# V2.net
KiCad netlist of a schematic drawn in Altium Designer
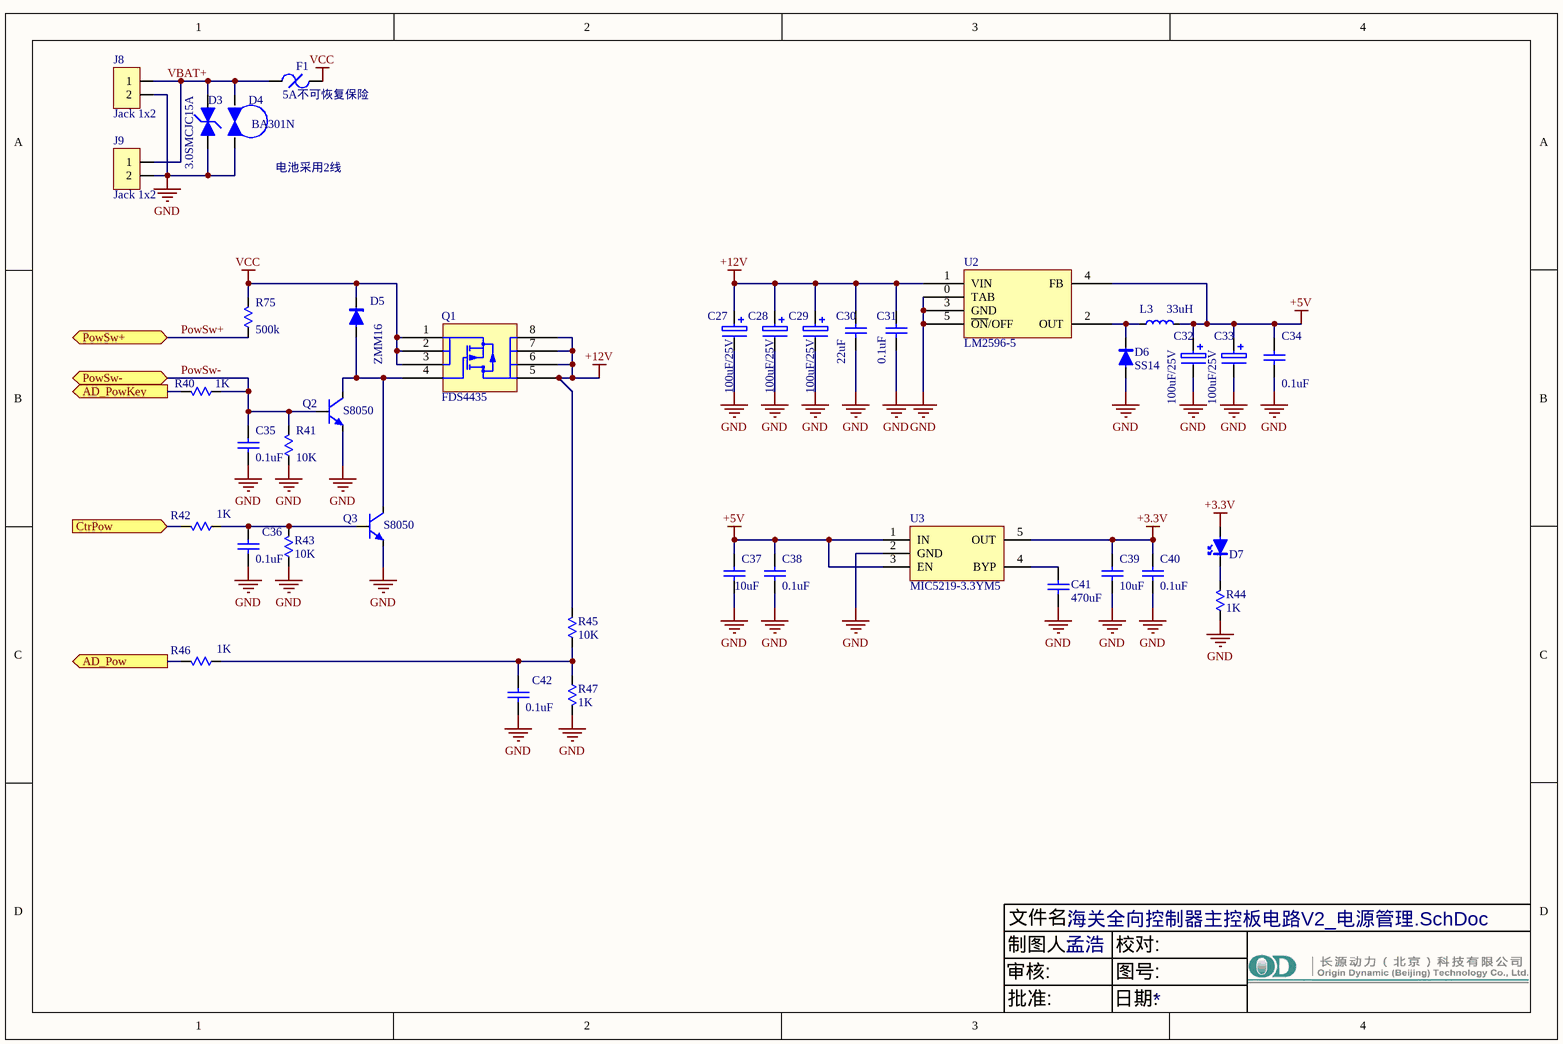
[diagram p0: 海关全向控制器主控板电路V2_电源管理.SchDoc]

(export (version "E")
  (design (tool "Eeschema 10.0.6"))
  (components
    (comp (ref "C27") (value "100uF/25V") (footprint "C7343") (libsource (lib "RLCYDF") (part "Cap Poll")))
    (comp (ref "C28") (value "100uF/25V") (footprint "C7343") (libsource (lib "RLCYDF") (part "Cap Poll")))
    (comp (ref "C29") (value "100uF/25V") (footprint "C7343") (libsource (lib "RLCYDF") (part "Cap Poll")))
    (comp (ref "C30")
      (value "22uF")
      (footprint "C1206")
      (description "CAP")
      (fields (field (name "PUBLISHER") "Altium Limited"))
      (libsource (lib "Passive Components Class") (part "CAP"))
    )
    (comp (ref "C31")
      (value "0.1uF")
      (footprint "C1206")
      (description "CAP")
      (fields (field (name "PUBLISHER") "Altium Limited"))
      (libsource (lib "Passive Components Class") (part "CAP"))
    )
    (comp (ref "C32")
      (value "100uF/25V")
      (footprint "C7343")
      (description "Electrolytic Capacitor")
      (libsource (lib "*") (part "ELECTRO"))
    )
    (comp (ref "C33")
      (value "100uF/25V")
      (footprint "C7343")
      (description "Electrolytic Capacitor")
      (libsource (lib "*") (part "ELECTRO"))
    )
    (comp (ref "C34")
      (value "0.1uF")
      (footprint "C0603")
      (description "CAP")
      (fields (field (name "PUBLISHER") "Altium Limited"))
      (libsource (lib "Passive Components Class") (part "CAP"))
    )
    (comp (ref "C35")
      (value "0.1uF")
      (footprint "C0603")
      (description "CAP")
      (fields (field (name "PUBLISHER") "Altium Limited"))
      (libsource (lib "Passive Components Class") (part "CAP"))
    )
    (comp (ref "C36")
      (value "0.1uF")
      (footprint "C0603")
      (description "CAP")
      (fields (field (name "PUBLISHER") "Altium Limited"))
      (libsource (lib "Passive Components Class") (part "CAP"))
    )
    (comp (ref "C37")
      (value "10uF")
      (footprint "C0603")
      (description "CAP")
      (fields (field (name "PUBLISHER") "Altium Limited"))
      (libsource (lib "Passive Components Class") (part "CAP"))
    )
    (comp (ref "C38")
      (value "0.1uF")
      (footprint "C0603")
      (description "CAP")
      (fields (field (name "PUBLISHER") "Altium Limited"))
      (libsource (lib "Passive Components Class") (part "CAP"))
    )
    (comp (ref "C39")
      (value "10uF")
      (footprint "C0603")
      (description "CAP")
      (fields (field (name "PUBLISHER") "Altium Limited"))
      (libsource (lib "Passive Components Class") (part "CAP"))
    )
    (comp (ref "C40")
      (value "0.1uF")
      (footprint "C0603")
      (description "CAP")
      (fields (field (name "PUBLISHER") "Altium Limited"))
      (libsource (lib "Passive Components Class") (part "CAP"))
    )
    (comp (ref "C41") (value "470uF") (footprint "C0603") (libsource (lib "SMD") (part "Cap Semi")))
    (comp (ref "C42")
      (value "0.1uF")
      (footprint "C0603")
      (description "CAP")
      (fields (field (name "PUBLISHER") "Altium Limited"))
      (libsource (lib "Passive Components Class") (part "CAP"))
    )
    (comp (ref "D3") (value "3.0SMCJC15A") (footprint "smc") (libsource (lib "RLCYDF") (part "Diode-TVS")))
    (comp (ref "D4") (value "BA301N") (footprint "BA301N") (libsource (lib "MhSchlib") (part "BA301N")))
    (comp (ref "D5")
      (value "ZMM16")
      (footprint "SOD-80-S")
      (description "Small Signal Zener Diodes")
      (libsource (lib "Passive Components Class") (part "DIODE-ZENER"))
    )
    (comp (ref "D6")
      (value "SS14")
      (footprint "SMA")
      (description "Silicon Epitaxial Planar Diodes")
      (libsource (lib "RLCYDF") (part "Diode-Switch"))
    )
    (comp (ref "D7")
      (value "LED")
      (footprint "LED0603")
      (libsource (lib "Passive Components Class") (part "LED"))
    )
    (comp (ref "F1") (value "5A不可恢复保险") (footprint "F1218") (libsource (lib "RLCYDF") (part "Fuse2")))
    (comp (ref "J8")
      (value "Jack 1x2")
      (footprint "ZH-2AWD")
      (description "插座")
      (libsource (lib "Connector") (part "Jack 1x2"))
    )
    (comp (ref "J9")
      (value "Jack 1x2")
      (footprint "ZH-2AWD")
      (description "插座")
      (libsource (lib "Connector") (part "Jack 1x2"))
    )
    (comp (ref "L3")
      (value "33uH")
      (footprint "L6.6*7.1mm")
      (description "INDUCTOR")
      (fields (field (name "PUBLISHER") "Altium Limited"))
      (libsource (lib "Passive Components Class") (part "INDUCTOR"))
    )
    (comp (ref "Q1") (value "FDS4435") (footprint "SO8") (libsource (lib "OmniDirCtr") (part "FDS4435")))
    (comp (ref "Q2")
      (value "S8050")
      (footprint "SOT-23")
      (description "NPN General Purpose Amplifier")
      (fields (field (name "PUBLISHER") "Altium Limited"))
      (libsource (lib "Bdmc4810") (part "NPN"))
    )
    (comp (ref "Q3")
      (value "S8050")
      (footprint "SOT-23")
      (description "NPN General Purpose Amplifier")
      (fields (field (name "PUBLISHER") "Altium Limited"))
      (libsource (lib "Bdmc4810") (part "NPN"))
    )
    (comp (ref "R40")
      (value "1K")
      (footprint "R0603")
      (description "Resistor")
      (fields (field (name "PUBLISHER") "Altium Limited"))
      (libsource (lib "Temp") (part "Res"))
    )
    (comp (ref "R41")
      (value "10K")
      (footprint "R0603")
      (description "Resistor")
      (fields (field (name "PUBLISHER") "Altium Limited"))
      (libsource (lib "Temp") (part "Res"))
    )
    (comp (ref "R42")
      (value "1K")
      (footprint "R0603")
      (description "Resistor")
      (fields (field (name "PUBLISHER") "Altium Limited"))
      (libsource (lib "Temp") (part "Res"))
    )
    (comp (ref "R43")
      (value "10K")
      (footprint "R0603")
      (description "Resistor")
      (fields (field (name "PUBLISHER") "Altium Limited"))
      (libsource (lib "Temp") (part "Res"))
    )
    (comp (ref "R44")
      (value "1K")
      (footprint "R0603")
      (description "Resistor")
      (fields (field (name "PUBLISHER") "Altium Limited"))
      (libsource (lib "UP-Robot") (part "Res"))
    )
    (comp (ref "R45")
      (value "10K")
      (footprint "R0603")
      (description "Resistor")
      (fields (field (name "PUBLISHER") "Altium Limited"))
      (libsource (lib "Temp") (part "Res"))
    )
    (comp (ref "R46")
      (value "1K")
      (footprint "R0603")
      (description "Resistor")
      (fields (field (name "PUBLISHER") "Altium Limited"))
      (libsource (lib "Temp") (part "Res"))
    )
    (comp (ref "R47")
      (value "1K")
      (footprint "R0603")
      (description "Resistor")
      (fields (field (name "PUBLISHER") "Altium Limited"))
      (libsource (lib "Temp") (part "Res"))
    )
    (comp (ref "R75")
      (value "500k")
      (footprint "R0603")
      (description "Resistor")
      (fields (field (name "PUBLISHER") "Altium Limited"))
      (libsource (lib "Temp") (part "Res"))
    )
    (comp (ref "U2")
      (value "LM2596-5")
      (footprint "TO-263-5")
      (description "LM2596-5;LM2576-5")
      (libsource (lib "chip") (part "LM25x6-5"))
    )
    (comp (ref "U3")
      (value "MIC5219-3.3YM5")
      (footprint "SOT-23-5")
      (libsource (lib "Power") (part "MIC5205"))
    )
  )
  (nets
    (net (code "1") (name "+3.3V") (class "Default")
      (node (ref "C39") (pin "1") (pinfunction "1_1") (pintype "passive"))
      (node (ref "C40") (pin "2") (pinfunction "2_2") (pintype "passive"))
      (node (ref "D7") (pin "1") (pinfunction "A_1") (pintype "passive"))
      (node (ref "U3") (pin "5") (pinfunction "OUT_5") (pintype "passive"))
    )
    (net (code "2") (name "+5V") (class "Default")
      (node (ref "C32") (pin "1") (pinfunction "1_1") (pintype "passive"))
      (node (ref "C33") (pin "1") (pinfunction "1_1") (pintype "passive"))
      (node (ref "C34") (pin "2") (pinfunction "2_2") (pintype "passive"))
      (node (ref "C37") (pin "1") (pinfunction "1_1") (pintype "passive"))
      (node (ref "C38") (pin "2") (pinfunction "2_2") (pintype "passive"))
      (node (ref "L3") (pin "2") (pinfunction "2_2") (pintype "passive"))
      (node (ref "U2") (pin "4") (pinfunction "FB_4") (pintype "passive"))
      (node (ref "U3") (pin "1") (pinfunction "IN_1") (pintype "passive"))
      (node (ref "U3") (pin "3") (pinfunction "EN_3") (pintype "passive"))
    )
    (net (code "3") (name "+12V") (class "Default")
      (node (ref "C27") (pin "1") (pinfunction "1_1") (pintype "passive"))
      (node (ref "C28") (pin "1") (pinfunction "1_1") (pintype "passive"))
      (node (ref "C29") (pin "1") (pinfunction "1_1") (pintype "passive"))
      (node (ref "C30") (pin "1") (pinfunction "1_1") (pintype "passive"))
      (node (ref "C31") (pin "1") (pinfunction "1_1") (pintype "passive"))
      (node (ref "Q1") (pin "5") (pintype "passive"))
      (node (ref "Q1") (pin "6") (pintype "passive"))
      (node (ref "Q1") (pin "7") (pintype "passive"))
      (node (ref "Q1") (pin "8") (pintype "passive"))
      (node (ref "R45") (pin "1") (pinfunction "1_1") (pintype "passive"))
      (node (ref "U2") (pin "1") (pinfunction "VIN_1") (pintype "passive"))
    )
    (net (code "4") (name "/AD_Pow") (class "Default")
      (node (ref "R46") (pin "1") (pinfunction "1_1") (pintype "passive"))
    )
    (net (code "5") (name "/AD_PowKey") (class "Default")
      (node (ref "R40") (pin "1") (pinfunction "1_1") (pintype "passive"))
    )
    (net (code "6") (name "/CtrPow") (class "Default")
      (node (ref "R42") (pin "1") (pinfunction "1_1") (pintype "passive"))
    )
    (net (code "7") (name "/PowSw+") (class "Default")
      (node (ref "R75") (pin "1") (pinfunction "1_1") (pintype "passive"))
    )
    (net (code "8") (name "/PowSw-") (class "Default")
      (node (ref "C35") (pin "2") (pinfunction "2_2") (pintype "passive"))
      (node (ref "Q2") (pin "1") (pinfunction "B_1") (pintype "passive"))
      (node (ref "R40") (pin "2") (pinfunction "2_2") (pintype "passive"))
      (node (ref "R41") (pin "1") (pinfunction "1_1") (pintype "passive"))
    )
    (net (code "9") (name "/VBAT+") (class "Default")
      (node (ref "D3") (pin "1") (pinfunction "A_1") (pintype "passive"))
      (node (ref "D4") (pin "1") (pinfunction "1_1") (pintype "passive"))
      (node (ref "F1") (pin "1") (pinfunction "1_1") (pintype "passive"))
      (node (ref "J8") (pin "1") (pinfunction "1_1") (pintype "passive"))
      (node (ref "J9") (pin "1") (pinfunction "1_1") (pintype "passive"))
    )
    (net (code "10") (name "GND") (class "Default")
      (node (ref "C27") (pin "2") (pinfunction "2_2") (pintype "passive"))
      (node (ref "C28") (pin "2") (pinfunction "2_2") (pintype "passive"))
      (node (ref "C29") (pin "2") (pinfunction "2_2") (pintype "passive"))
      (node (ref "C30") (pin "2") (pinfunction "2_2") (pintype "passive"))
      (node (ref "C31") (pin "2") (pinfunction "2_2") (pintype "passive"))
      (node (ref "C32") (pin "2") (pinfunction "2_2") (pintype "passive"))
      (node (ref "C33") (pin "2") (pinfunction "2_2") (pintype "passive"))
      (node (ref "C34") (pin "1") (pinfunction "1_1") (pintype "passive"))
      (node (ref "C35") (pin "1") (pinfunction "1_1") (pintype "passive"))
      (node (ref "C36") (pin "1") (pinfunction "1_1") (pintype "passive"))
      (node (ref "C37") (pin "2") (pinfunction "2_2") (pintype "passive"))
      (node (ref "C38") (pin "1") (pinfunction "1_1") (pintype "passive"))
      (node (ref "C39") (pin "2") (pinfunction "2_2") (pintype "passive"))
      (node (ref "C40") (pin "1") (pinfunction "1_1") (pintype "passive"))
      (node (ref "C41") (pin "1") (pinfunction "1_1") (pintype "passive"))
      (node (ref "C42") (pin "1") (pinfunction "1_1") (pintype "passive"))
      (node (ref "D3") (pin "2") (pinfunction "K_2") (pintype "passive"))
      (node (ref "D4") (pin "2") (pinfunction "2_2") (pintype "passive"))
      (node (ref "D6") (pin "1") (pinfunction "A_1") (pintype "passive"))
      (node (ref "J8") (pin "2") (pinfunction "2_2") (pintype "passive"))
      (node (ref "J9") (pin "2") (pinfunction "2_2") (pintype "passive"))
      (node (ref "Q2") (pin "2") (pinfunction "E_2") (pintype "passive"))
      (node (ref "Q3") (pin "2") (pinfunction "E_2") (pintype "passive"))
      (node (ref "R41") (pin "2") (pinfunction "2_2") (pintype "passive"))
      (node (ref "R43") (pin "2") (pinfunction "2_2") (pintype "passive"))
      (node (ref "R44") (pin "1") (pinfunction "1_1") (pintype "passive"))
      (node (ref "R47") (pin "1") (pinfunction "1_1") (pintype "passive"))
      (node (ref "U2") (pin "0") (pinfunction "TAB_0") (pintype "passive"))
      (node (ref "U2") (pin "3") (pinfunction "GND_3") (pintype "passive"))
      (node (ref "U2") (pin "5") (pinfunction "~{ON}/OFF_5") (pintype "passive"))
      (node (ref "U3") (pin "2") (pinfunction "GND_2") (pintype "passive"))
    )
    (net (code "11") (name "Net-(C42-Pad2)") (class "Default")
      (node (ref "C42") (pin "2") (pinfunction "2_2") (pintype "passive"))
      (node (ref "R45") (pin "2") (pinfunction "2_2") (pintype "passive"))
      (node (ref "R46") (pin "2") (pinfunction "2_2") (pintype "passive"))
      (node (ref "R47") (pin "2") (pinfunction "2_2") (pintype "passive"))
    )
    (net (code "12") (name "Net-(D5-A)") (class "Default")
      (node (ref "D5") (pin "1") (pinfunction "A_1") (pintype "passive"))
      (node (ref "Q1") (pin "4") (pintype "passive"))
      (node (ref "Q2") (pin "3") (pinfunction "C_3") (pintype "passive"))
      (node (ref "Q3") (pin "3") (pinfunction "C_3") (pintype "passive"))
    )
    (net (code "13") (name "Net-(D6-K)") (class "Default")
      (node (ref "D6") (pin "2") (pinfunction "K_2") (pintype "passive"))
      (node (ref "L3") (pin "1") (pinfunction "1_1") (pintype "passive"))
      (node (ref "U2") (pin "2") (pinfunction "OUT_2") (pintype "passive"))
    )
    (net (code "14") (name "Net-(D7-K)") (class "Default")
      (node (ref "D7") (pin "2") (pinfunction "K_2") (pintype "passive"))
      (node (ref "R44") (pin "2") (pinfunction "2_2") (pintype "passive"))
    )
    (net (code "15") (name "Net-(Q3-B)") (class "Default")
      (node (ref "C36") (pin "2") (pinfunction "2_2") (pintype "passive"))
      (node (ref "Q3") (pin "1") (pinfunction "B_1") (pintype "passive"))
      (node (ref "R42") (pin "2") (pinfunction "2_2") (pintype "passive"))
      (node (ref "R43") (pin "1") (pinfunction "1_1") (pintype "passive"))
    )
    (net (code "16") (name "Net-(U3-BYP)") (class "Default")
      (node (ref "C41") (pin "2") (pinfunction "2_2") (pintype "passive"))
      (node (ref "U3") (pin "4") (pinfunction "BYP_4") (pintype "passive"))
    )
    (net (code "17") (name "VCC") (class "Default")
      (node (ref "D5") (pin "2") (pinfunction "K_2") (pintype "passive"))
      (node (ref "F1") (pin "2") (pinfunction "2_2") (pintype "passive"))
      (node (ref "Q1") (pin "1") (pintype "passive"))
      (node (ref "Q1") (pin "2") (pintype "passive"))
      (node (ref "Q1") (pin "3") (pintype "passive"))
      (node (ref "R75") (pin "2") (pinfunction "2_2") (pintype "passive"))
    )
  )
)
